# medusa-ai-audio.net
KiCad netlist of a schematic drawn in Altium Designer
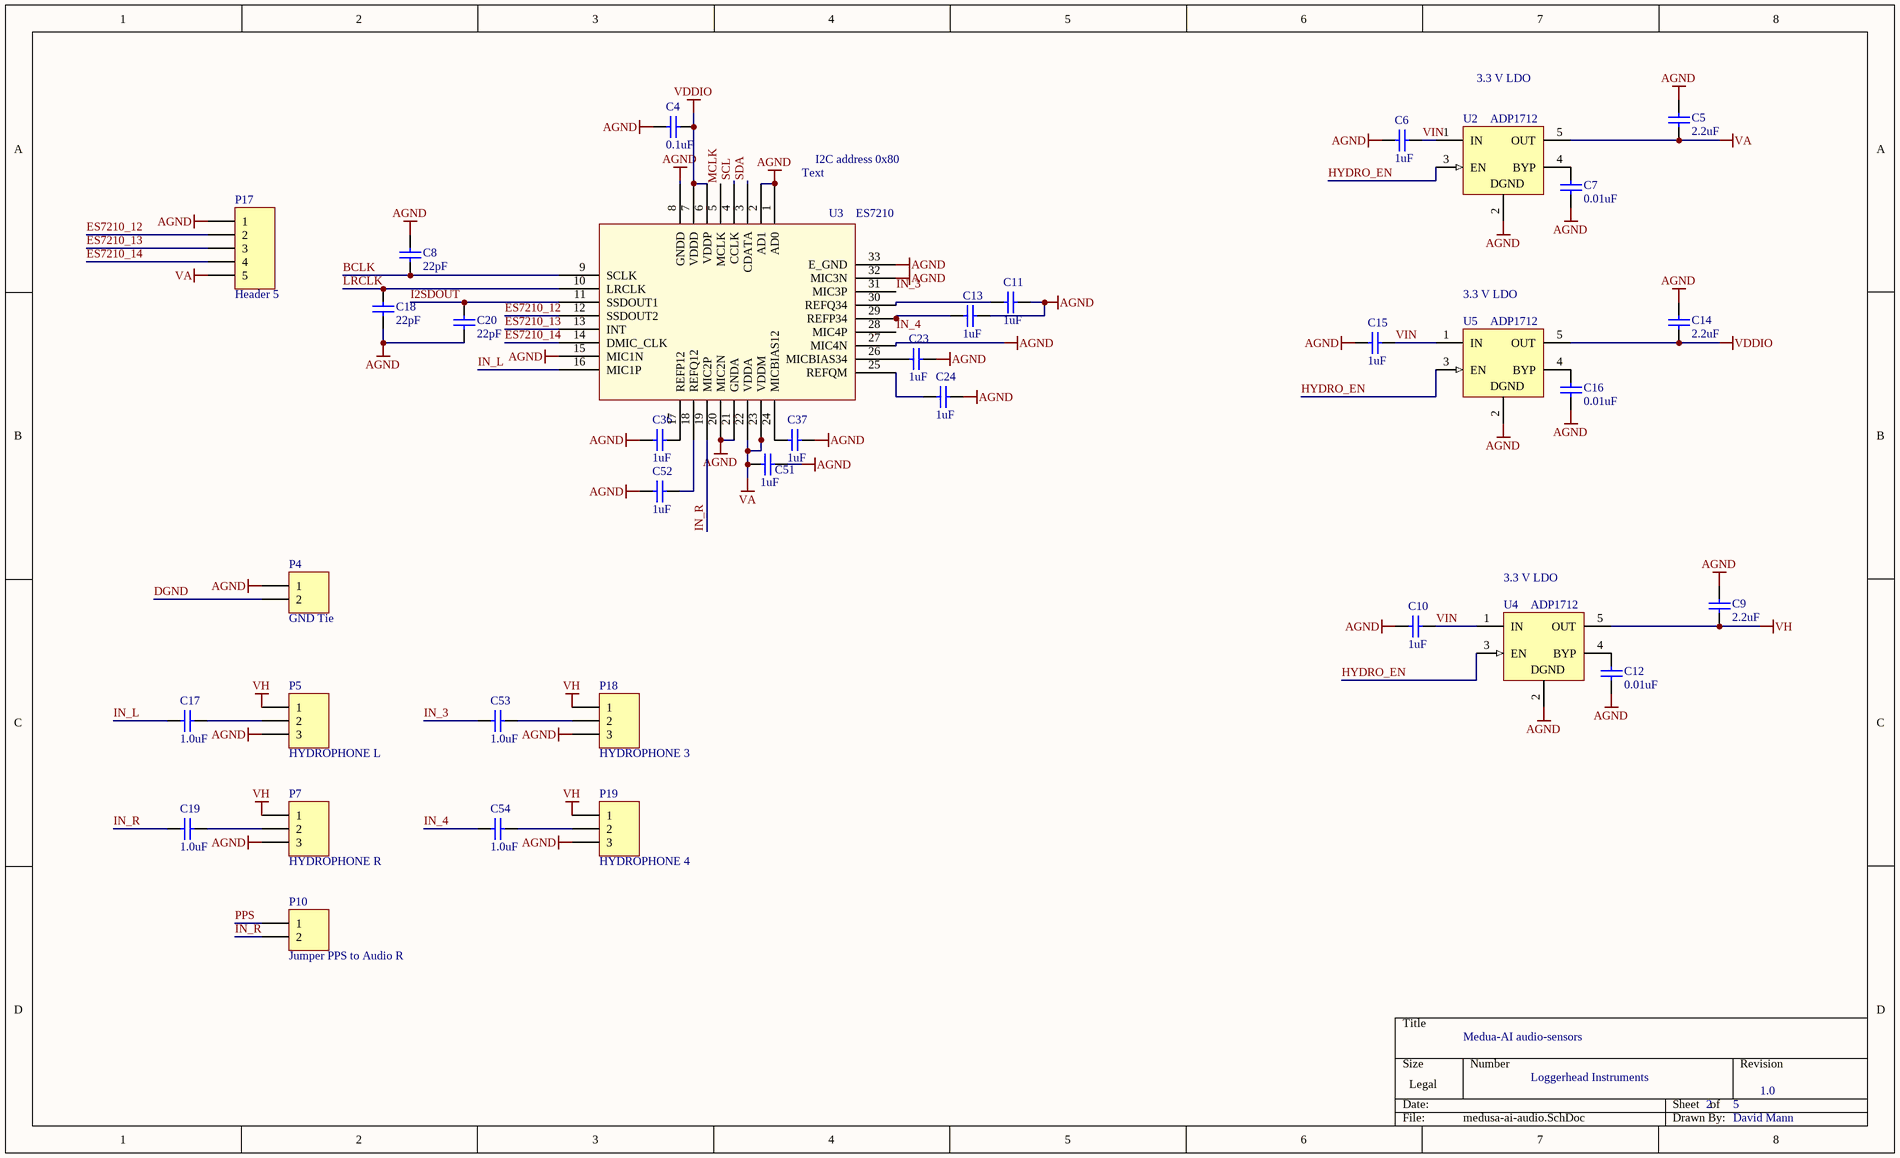
[diagram p0: medusa-ai-audio.SchDoc]

(export (version "E")
  (design (tool "Eeschema 10.0.6"))
  (components
    (comp (ref "C4")
      (value "0.1uF")
      (footprint "0402")
      (description "Ceramic Chip Capacitor - Standard")
      (fields (field (name "PUBLISHER") "Altium Limited"))
      (libsource (lib "KEMET Chip Capacitor") (part "C0402"))
    )
    (comp (ref "C5")
      (value "2.2uF")
      (footprint "0402")
      (description "Ceramic Chip Capacitor - Standard")
      (fields (field (name "PUBLISHER") "Altium Limited"))
      (libsource (lib "KEMET Chip Capacitor") (part "C0402"))
    )
    (comp (ref "C6")
      (value "1uF")
      (footprint "0402")
      (description "Ceramic Chip Capacitor - Standard")
      (fields (field (name "PUBLISHER") "Altium Limited"))
      (libsource (lib "KEMET Chip Capacitor") (part "C0402"))
    )
    (comp (ref "C7")
      (value "0.01uF")
      (footprint "0402")
      (description "Ceramic Chip Capacitor - Standard")
      (fields (field (name "PUBLISHER") "Altium Limited"))
      (libsource (lib "KEMET Chip Capacitor") (part "C0402"))
    )
    (comp (ref "C8")
      (value "22pF")
      (footprint "0402")
      (description "Ceramic Chip Capacitor - Standard")
      (fields (field (name "PUBLISHER") "Altium Limited"))
      (libsource (lib "KEMET Chip Capacitor") (part "C0402"))
    )
    (comp (ref "C9")
      (value "2.2uF")
      (footprint "0402")
      (description "Ceramic Chip Capacitor - Standard")
      (fields (field (name "PUBLISHER") "Altium Limited"))
      (libsource (lib "KEMET Chip Capacitor") (part "C0402"))
    )
    (comp (ref "C10")
      (value "1uF")
      (footprint "0402")
      (description "Ceramic Chip Capacitor - Standard")
      (fields (field (name "PUBLISHER") "Altium Limited"))
      (libsource (lib "KEMET Chip Capacitor") (part "C0402"))
    )
    (comp (ref "C11")
      (value "1uF")
      (footprint "0402")
      (description "Ceramic Chip Capacitor - Standard")
      (fields (field (name "PUBLISHER") "Altium Limited"))
      (libsource (lib "KEMET Chip Capacitor") (part "C0402"))
    )
    (comp (ref "C12")
      (value "0.01uF")
      (footprint "0402")
      (description "Ceramic Chip Capacitor - Standard")
      (fields (field (name "PUBLISHER") "Altium Limited"))
      (libsource (lib "KEMET Chip Capacitor") (part "C0402"))
    )
    (comp (ref "C13")
      (value "1uF")
      (footprint "0402")
      (description "Ceramic Chip Capacitor - Standard")
      (fields (field (name "PUBLISHER") "Altium Limited"))
      (libsource (lib "KEMET Chip Capacitor") (part "C0402"))
    )
    (comp (ref "C14")
      (value "2.2uF")
      (footprint "0402")
      (description "Ceramic Chip Capacitor - Standard")
      (fields (field (name "PUBLISHER") "Altium Limited"))
      (libsource (lib "KEMET Chip Capacitor") (part "C0402"))
    )
    (comp (ref "C15")
      (value "1uF")
      (footprint "0402")
      (description "Ceramic Chip Capacitor - Standard")
      (fields (field (name "PUBLISHER") "Altium Limited"))
      (libsource (lib "KEMET Chip Capacitor") (part "C0402"))
    )
    (comp (ref "C16")
      (value "0.01uF")
      (footprint "0402")
      (description "Ceramic Chip Capacitor - Standard")
      (fields (field (name "PUBLISHER") "Altium Limited"))
      (libsource (lib "KEMET Chip Capacitor") (part "C0402"))
    )
    (comp (ref "C17")
      (value "1.0uF")
      (footprint "0402")
      (description "Ceramic Chip Capacitor - Standard")
      (fields (field (name "PUBLISHER") "Altium Limited"))
      (libsource (lib "KEMET Chip Capacitor") (part "C0402"))
    )
    (comp (ref "C18")
      (value "22pF")
      (footprint "0402")
      (description "Ceramic Chip Capacitor - Standard")
      (fields (field (name "PUBLISHER") "Altium Limited"))
      (libsource (lib "KEMET Chip Capacitor") (part "C0402"))
    )
    (comp (ref "C19")
      (value "1.0uF")
      (footprint "0402")
      (description "Ceramic Chip Capacitor - Standard")
      (fields (field (name "PUBLISHER") "Altium Limited"))
      (libsource (lib "KEMET Chip Capacitor") (part "C0402"))
    )
    (comp (ref "C20")
      (value "22pF")
      (footprint "0402")
      (description "Ceramic Chip Capacitor - Standard")
      (fields (field (name "PUBLISHER") "Altium Limited"))
      (libsource (lib "KEMET Chip Capacitor") (part "C0402"))
    )
    (comp (ref "C23")
      (value "1uF")
      (footprint "0402")
      (description "Ceramic Chip Capacitor - Standard")
      (fields (field (name "PUBLISHER") "Altium Limited"))
      (libsource (lib "KEMET Chip Capacitor") (part "C0402"))
    )
    (comp (ref "C24")
      (value "1uF")
      (footprint "0402")
      (description "Ceramic Chip Capacitor - Standard")
      (fields (field (name "PUBLISHER") "Altium Limited"))
      (libsource (lib "KEMET Chip Capacitor") (part "C0402"))
    )
    (comp (ref "C36")
      (value "1uF")
      (footprint "0402")
      (description "Ceramic Chip Capacitor - Standard")
      (fields (field (name "PUBLISHER") "Altium Limited"))
      (libsource (lib "KEMET Chip Capacitor") (part "C0402"))
    )
    (comp (ref "C37")
      (value "1uF")
      (footprint "0402")
      (description "Ceramic Chip Capacitor - Standard")
      (fields (field (name "PUBLISHER") "Altium Limited"))
      (libsource (lib "KEMET Chip Capacitor") (part "C0402"))
    )
    (comp (ref "C51")
      (value "1uF")
      (footprint "0402")
      (description "Ceramic Chip Capacitor - Standard")
      (fields (field (name "PUBLISHER") "Altium Limited"))
      (libsource (lib "KEMET Chip Capacitor") (part "C0402"))
    )
    (comp (ref "C52")
      (value "1uF")
      (footprint "0402")
      (description "Ceramic Chip Capacitor - Standard")
      (fields (field (name "PUBLISHER") "Altium Limited"))
      (libsource (lib "KEMET Chip Capacitor") (part "C0402"))
    )
    (comp (ref "C53")
      (value "1.0uF")
      (footprint "0402")
      (description "Ceramic Chip Capacitor - Standard")
      (fields (field (name "PUBLISHER") "Altium Limited"))
      (libsource (lib "KEMET Chip Capacitor") (part "C0402"))
    )
    (comp (ref "C54")
      (value "1.0uF")
      (footprint "0402")
      (description "Ceramic Chip Capacitor - Standard")
      (fields (field (name "PUBLISHER") "Altium Limited"))
      (libsource (lib "KEMET Chip Capacitor") (part "C0402"))
    )
    (comp (ref "P4")
      (value "GND Tie")
      (footprint "HDR1X2")
      (description "Header, 2-Pin")
      (fields (field (name "PUBLISHER") "Altium Limited"))
      (libsource (lib "Miscellaneous Connectors") (part "Header 2"))
    )
    (comp (ref "P5")
      (value "HYDROPHONE L")
      (footprint "HDR1X3")
      (description "Header, 3-Pin")
      (fields (field (name "PUBLISHER") "Altium Limited"))
      (libsource (lib "Miscellaneous Connectors") (part "Header 3"))
    )
    (comp (ref "P7")
      (value "HYDROPHONE R")
      (footprint "HDR1X3")
      (description "Header, 3-Pin")
      (fields (field (name "PUBLISHER") "Altium Limited"))
      (libsource (lib "Miscellaneous Connectors") (part "Header 3"))
    )
    (comp (ref "P10")
      (value "Jumper PPS to Audio R")
      (footprint "HDR1X2")
      (description "Header, 2-Pin")
      (fields (field (name "PUBLISHER") "Altium Limited"))
      (libsource (lib "Miscellaneous Connectors") (part "Header 2"))
    )
    (comp (ref "P17")
      (value "Header 5")
      (footprint "HDR1X5")
      (description "Header, 5-Pin")
      (fields (field (name "PUBLISHER") "Altium Limited"))
      (libsource (lib "Miscellaneous Connectors") (part "Header 5"))
    )
    (comp (ref "P18")
      (value "HYDROPHONE 3")
      (footprint "HDR1X3")
      (description "Header, 3-Pin")
      (fields (field (name "PUBLISHER") "Altium Limited"))
      (libsource (lib "Miscellaneous Connectors") (part "Header 3"))
    )
    (comp (ref "P19")
      (value "HYDROPHONE 4")
      (footprint "HDR1X3")
      (description "Header, 3-Pin")
      (fields (field (name "PUBLISHER") "Altium Limited"))
      (libsource (lib "Miscellaneous Connectors") (part "Header 3"))
    )
    (comp (ref "U2")
      (value "ADP1712")
      (footprint "MF05A_N")
      (description "Micropower, 150mA Low-Noise Ultra Low-Dropout CMOS Voltage Regulator")
      (fields
        (field (name "PARTNUMBER") "LP3985IM5-3.3")
        (field (name "MANUFACTURER") "National Semiconductor")
        (field (name "PUBLISHER") "Altium Limited")
      )
      (libsource (lib "NSC LDO") (part "LP3985IM5-3.3"))
    )
    (comp (ref "U3")
      (value "ES7210")
      (footprint "ES7210")
      (description "Audio CODEC")
      (libsource (lib "Loggerhead") (part "ES7210"))
    )
    (comp (ref "U4")
      (value "ADP1712")
      (footprint "MF05A_N")
      (description "Micropower, 150mA Low-Noise Ultra Low-Dropout CMOS Voltage Regulator")
      (fields
        (field (name "PARTNUMBER") "LP3985IM5-3.3")
        (field (name "MANUFACTURER") "National Semiconductor")
        (field (name "PUBLISHER") "Altium Limited")
      )
      (libsource (lib "NSC LDO") (part "LP3985IM5-3.3"))
    )
    (comp (ref "U5")
      (value "ADP1712")
      (footprint "MF05A_N")
      (description "Micropower, 150mA Low-Noise Ultra Low-Dropout CMOS Voltage Regulator")
      (fields
        (field (name "PARTNUMBER") "LP3985IM5-3.3")
        (field (name "MANUFACTURER") "National Semiconductor")
        (field (name "PUBLISHER") "Altium Limited")
      )
      (libsource (lib "NSC LDO") (part "LP3985IM5-3.3"))
    )
  )
  (nets
    (net (code "1") (name "/BCLK") (class "Default")
      (node (ref "C8") (pin "2") (pinfunction "2_2") (pintype "passive"))
      (node (ref "U3") (pin "9") (pinfunction "SCLK_9") (pintype "passive"))
    )
    (net (code "2") (name "/DGND") (class "Default")
      (node (ref "P4") (pin "2") (pinfunction "2_2") (pintype "passive"))
    )
    (net (code "3") (name "/ES7210_12") (class "Default")
      (node (ref "P17") (pin "2") (pinfunction "2_2") (pintype "passive"))
      (node (ref "U3") (pin "12") (pinfunction "SSDOUT2_12") (pintype "passive"))
    )
    (net (code "4") (name "/ES7210_13") (class "Default")
      (node (ref "P17") (pin "3") (pinfunction "3_3") (pintype "passive"))
      (node (ref "U3") (pin "13") (pinfunction "INT_13") (pintype "passive"))
    )
    (net (code "5") (name "/ES7210_14") (class "Default")
      (node (ref "P17") (pin "4") (pinfunction "4_4") (pintype "passive"))
      (node (ref "U3") (pin "14") (pinfunction "DMIC_CLK_14") (pintype "passive"))
    )
    (net (code "6") (name "/HYDRO_EN") (class "Default")
      (node (ref "U2") (pin "3") (pinfunction "EN_3") (pintype "input"))
      (node (ref "U4") (pin "3") (pinfunction "EN_3") (pintype "input"))
      (node (ref "U5") (pin "3") (pinfunction "EN_3") (pintype "input"))
    )
    (net (code "7") (name "/I2SDOUT") (class "Default")
      (node (ref "C20") (pin "1") (pinfunction "1_1") (pintype "passive"))
      (node (ref "U3") (pin "11") (pinfunction "SSDOUT1_11") (pintype "passive"))
    )
    (net (code "8") (name "/IN_3") (class "Default")
      (node (ref "C53") (pin "2") (pinfunction "2_2") (pintype "passive"))
      (node (ref "U3") (pin "31") (pinfunction "MIC3P_31") (pintype "passive"))
    )
    (net (code "9") (name "/IN_4") (class "Default")
      (node (ref "C54") (pin "2") (pinfunction "2_2") (pintype "passive"))
      (node (ref "U3") (pin "28") (pinfunction "MIC4P_28") (pintype "passive"))
    )
    (net (code "10") (name "/IN_L") (class "Default")
      (node (ref "C17") (pin "2") (pinfunction "2_2") (pintype "passive"))
      (node (ref "U3") (pin "16") (pinfunction "MIC1P_16") (pintype "passive"))
    )
    (net (code "11") (name "/IN_R") (class "Default")
      (node (ref "C19") (pin "2") (pinfunction "2_2") (pintype "passive"))
      (node (ref "P10") (pin "2") (pinfunction "2_2") (pintype "passive"))
      (node (ref "U3") (pin "19") (pinfunction "MIC2P_19") (pintype "passive"))
    )
    (net (code "12") (name "/LRCLK") (class "Default")
      (node (ref "C18") (pin "1") (pinfunction "1_1") (pintype "passive"))
      (node (ref "U3") (pin "10") (pinfunction "LRCLK_10") (pintype "passive"))
    )
    (net (code "13") (name "/MCLK") (class "Default")
      (node (ref "U3") (pin "5") (pinfunction "MCLK_5") (pintype "passive"))
    )
    (net (code "14") (name "/PPS") (class "Default")
      (node (ref "P10") (pin "1") (pinfunction "1_1") (pintype "passive"))
    )
    (net (code "15") (name "/SCL") (class "Default")
      (node (ref "U3") (pin "4") (pinfunction "CCLK_4") (pintype "passive"))
    )
    (net (code "16") (name "/SDA") (class "Default")
      (node (ref "U3") (pin "3") (pinfunction "CDATA_3") (pintype "passive"))
    )
    (net (code "17") (name "/VIN") (class "Default")
      (node (ref "C10") (pin "1") (pinfunction "1_1") (pintype "passive"))
      (node (ref "C15") (pin "1") (pinfunction "1_1") (pintype "passive"))
      (node (ref "C6") (pin "1") (pinfunction "1_1") (pintype "passive"))
      (node (ref "U2") (pin "1") (pinfunction "IN_1") (pintype "power_in"))
      (node (ref "U4") (pin "1") (pinfunction "IN_1") (pintype "power_in"))
      (node (ref "U5") (pin "1") (pinfunction "IN_1") (pintype "power_in"))
    )
    (net (code "18") (name "AGND") (class "Default")
      (node (ref "C10") (pin "2") (pinfunction "2_2") (pintype "passive"))
      (node (ref "C11") (pin "1") (pinfunction "1_1") (pintype "passive"))
      (node (ref "C12") (pin "2") (pinfunction "2_2") (pintype "passive"))
      (node (ref "C13") (pin "1") (pinfunction "1_1") (pintype "passive"))
      (node (ref "C14") (pin "2") (pinfunction "2_2") (pintype "passive"))
      (node (ref "C15") (pin "2") (pinfunction "2_2") (pintype "passive"))
      (node (ref "C16") (pin "2") (pinfunction "2_2") (pintype "passive"))
      (node (ref "C18") (pin "2") (pinfunction "2_2") (pintype "passive"))
      (node (ref "C20") (pin "2") (pinfunction "2_2") (pintype "passive"))
      (node (ref "C23") (pin "1") (pinfunction "1_1") (pintype "passive"))
      (node (ref "C24") (pin "1") (pinfunction "1_1") (pintype "passive"))
      (node (ref "C36") (pin "2") (pinfunction "2_2") (pintype "passive"))
      (node (ref "C37") (pin "1") (pinfunction "1_1") (pintype "passive"))
      (node (ref "C4") (pin "1") (pinfunction "1_1") (pintype "passive"))
      (node (ref "C5") (pin "2") (pinfunction "2_2") (pintype "passive"))
      (node (ref "C51") (pin "1") (pinfunction "1_1") (pintype "passive"))
      (node (ref "C52") (pin "1") (pinfunction "1_1") (pintype "passive"))
      (node (ref "C6") (pin "2") (pinfunction "2_2") (pintype "passive"))
      (node (ref "C7") (pin "2") (pinfunction "2_2") (pintype "passive"))
      (node (ref "C8") (pin "1") (pinfunction "1_1") (pintype "passive"))
      (node (ref "C9") (pin "2") (pinfunction "2_2") (pintype "passive"))
      (node (ref "P17") (pin "1") (pinfunction "1_1") (pintype "passive"))
      (node (ref "P18") (pin "3") (pinfunction "3_3") (pintype "passive"))
      (node (ref "P19") (pin "3") (pinfunction "3_3") (pintype "passive"))
      (node (ref "P4") (pin "1") (pinfunction "1_1") (pintype "passive"))
      (node (ref "P5") (pin "3") (pinfunction "3_3") (pintype "passive"))
      (node (ref "P7") (pin "3") (pinfunction "3_3") (pintype "passive"))
      (node (ref "U2") (pin "2") (pinfunction "GND_2") (pintype "power_in"))
      (node (ref "U3") (pin "1") (pinfunction "AD0_1") (pintype "passive"))
      (node (ref "U3") (pin "15") (pinfunction "MIC1N_15") (pintype "passive"))
      (node (ref "U3") (pin "2") (pinfunction "AD1_2") (pintype "passive"))
      (node (ref "U3") (pin "20") (pinfunction "MIC2N_20") (pintype "passive"))
      (node (ref "U3") (pin "21") (pinfunction "GNDA_21") (pintype "passive"))
      (node (ref "U3") (pin "27") (pinfunction "MIC4N_27") (pintype "passive"))
      (node (ref "U3") (pin "32") (pinfunction "MIC3N_32") (pintype "passive"))
      (node (ref "U3") (pin "33") (pinfunction "E_GND_33") (pintype "passive"))
      (node (ref "U3") (pin "8") (pinfunction "GNDD_8") (pintype "passive"))
      (node (ref "U4") (pin "2") (pinfunction "GND_2") (pintype "power_in"))
      (node (ref "U5") (pin "2") (pinfunction "GND_2") (pintype "power_in"))
    )
    (net (code "19") (name "Net-(C17-Pad1)") (class "Default")
      (node (ref "C17") (pin "1") (pinfunction "1_1") (pintype "passive"))
      (node (ref "P5") (pin "2") (pinfunction "2_2") (pintype "passive"))
    )
    (net (code "20") (name "Net-(C19-Pad1)") (class "Default")
      (node (ref "C19") (pin "1") (pinfunction "1_1") (pintype "passive"))
      (node (ref "P7") (pin "2") (pinfunction "2_2") (pintype "passive"))
    )
    (net (code "21") (name "Net-(C53-Pad1)") (class "Default")
      (node (ref "C53") (pin "1") (pinfunction "1_1") (pintype "passive"))
      (node (ref "P18") (pin "2") (pinfunction "2_2") (pintype "passive"))
    )
    (net (code "22") (name "Net-(C54-Pad1)") (class "Default")
      (node (ref "C54") (pin "1") (pinfunction "1_1") (pintype "passive"))
      (node (ref "P19") (pin "2") (pinfunction "2_2") (pintype "passive"))
    )
    (net (code "23") (name "Net-(U2-BYP)") (class "Default")
      (node (ref "C7") (pin "1") (pinfunction "1_1") (pintype "passive"))
      (node (ref "U2") (pin "4") (pinfunction "BYP_4") (pintype "passive"))
    )
    (net (code "24") (name "Net-(U3-MICBIAS12)") (class "Default")
      (node (ref "C37") (pin "2") (pinfunction "2_2") (pintype "passive"))
      (node (ref "U3") (pin "24") (pinfunction "MICBIAS12_24") (pintype "passive"))
    )
    (net (code "25") (name "Net-(U3-MICBIAS34)") (class "Default")
      (node (ref "C23") (pin "2") (pinfunction "2_2") (pintype "passive"))
      (node (ref "U3") (pin "26") (pinfunction "MICBIAS34_26") (pintype "passive"))
    )
    (net (code "26") (name "Net-(U3-REFP12)") (class "Default")
      (node (ref "C36") (pin "1") (pinfunction "1_1") (pintype "passive"))
      (node (ref "U3") (pin "17") (pinfunction "REFP12_17") (pintype "passive"))
    )
    (net (code "27") (name "Net-(U3-REFP34)") (class "Default")
      (node (ref "C13") (pin "2") (pinfunction "2_2") (pintype "passive"))
      (node (ref "U3") (pin "29") (pinfunction "REFP34_29") (pintype "passive"))
    )
    (net (code "28") (name "Net-(U3-REFQ12)") (class "Default")
      (node (ref "C52") (pin "2") (pinfunction "2_2") (pintype "passive"))
      (node (ref "U3") (pin "18") (pinfunction "REFQ12_18") (pintype "passive"))
    )
    (net (code "29") (name "Net-(U3-REFQ34)") (class "Default")
      (node (ref "C11") (pin "2") (pinfunction "2_2") (pintype "passive"))
      (node (ref "U3") (pin "30") (pinfunction "REFQ34_30") (pintype "passive"))
    )
    (net (code "30") (name "Net-(U3-REFQM)") (class "Default")
      (node (ref "C24") (pin "2") (pinfunction "2_2") (pintype "passive"))
      (node (ref "U3") (pin "25") (pinfunction "REFQM_25") (pintype "passive"))
    )
    (net (code "31") (name "Net-(U4-BYP)") (class "Default")
      (node (ref "C12") (pin "1") (pinfunction "1_1") (pintype "passive"))
      (node (ref "U4") (pin "4") (pinfunction "BYP_4") (pintype "passive"))
    )
    (net (code "32") (name "Net-(U5-BYP)") (class "Default")
      (node (ref "C16") (pin "1") (pinfunction "1_1") (pintype "passive"))
      (node (ref "U5") (pin "4") (pinfunction "BYP_4") (pintype "passive"))
    )
    (net (code "33") (name "VA") (class "Default")
      (node (ref "C5") (pin "1") (pinfunction "1_1") (pintype "passive"))
      (node (ref "C51") (pin "2") (pinfunction "2_2") (pintype "passive"))
      (node (ref "P17") (pin "5") (pinfunction "5_5") (pintype "passive"))
      (node (ref "U2") (pin "5") (pinfunction "OUT_5") (pintype "power_in"))
      (node (ref "U3") (pin "22") (pinfunction "VDDA_22") (pintype "passive"))
      (node (ref "U3") (pin "23") (pinfunction "VDDM_23") (pintype "passive"))
    )
    (net (code "34") (name "VDDIO") (class "Default")
      (node (ref "C14") (pin "1") (pinfunction "1_1") (pintype "passive"))
      (node (ref "C4") (pin "2") (pinfunction "2_2") (pintype "passive"))
      (node (ref "U3") (pin "6") (pinfunction "VDDP_6") (pintype "passive"))
      (node (ref "U3") (pin "7") (pinfunction "VDDD_7") (pintype "passive"))
      (node (ref "U5") (pin "5") (pinfunction "OUT_5") (pintype "power_in"))
    )
    (net (code "35") (name "VH") (class "Default")
      (node (ref "C9") (pin "1") (pinfunction "1_1") (pintype "passive"))
      (node (ref "P18") (pin "1") (pinfunction "1_1") (pintype "passive"))
      (node (ref "P19") (pin "1") (pinfunction "1_1") (pintype "passive"))
      (node (ref "P5") (pin "1") (pinfunction "1_1") (pintype "passive"))
      (node (ref "P7") (pin "1") (pinfunction "1_1") (pintype "passive"))
      (node (ref "U4") (pin "5") (pinfunction "OUT_5") (pintype "power_in"))
    )
  )
)
